# ESP8266-CT-EVB.net
KiCad netlist of a schematic drawn in EAGLE
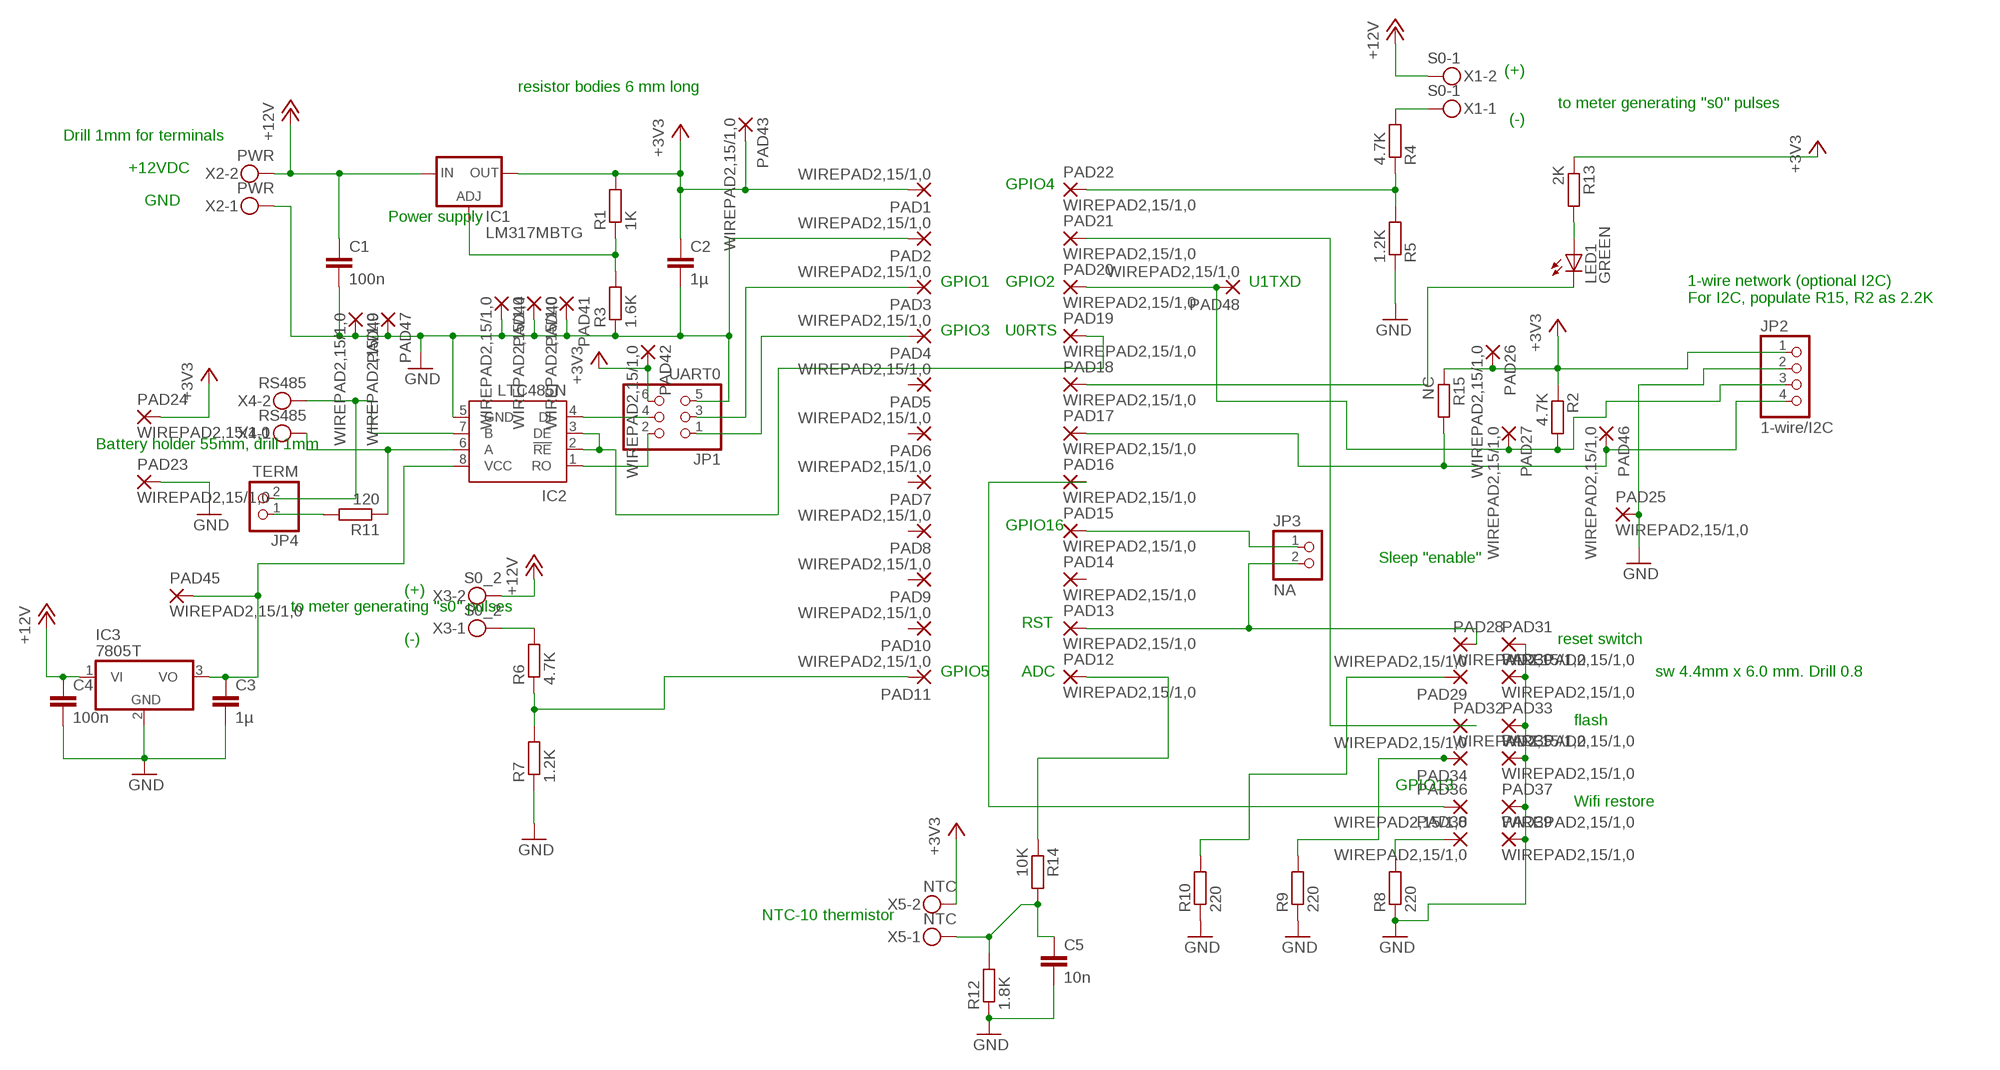
[diagram p0: schematic, sheet 1]

(export (version "E")
  (design (tool "Eeschema 10.0.6"))
  (components
    (comp (ref "C1")
      (value "100n")
      (footprint "eagle-import:C050-024X044")
      (libsource (lib "eagle-import") (part "C-EU050-024X044"))
    )
    (comp (ref "C2")
      (value "1µ")
      (footprint "eagle-import:C050-024X044")
      (libsource (lib "eagle-import") (part "C-EU050-024X044"))
    )
    (comp (ref "C3")
      (value "1µ")
      (footprint "eagle-import:C050-024X044")
      (libsource (lib "eagle-import") (part "C-EU050-024X044"))
    )
    (comp (ref "C4")
      (value "100n")
      (footprint "eagle-import:C050-024X044")
      (libsource (lib "eagle-import") (part "C-EU050-024X044"))
    )
    (comp (ref "C5")
      (value "10n")
      (footprint "eagle-import:C050-024X044")
      (libsource (lib "eagle-import") (part "C-EU050-024X044"))
    )
    (comp (ref "IC1")
      (value "LM317MBTG")
      (footprint "eagle-import:TO220L1")
      (libsource (lib "eagle-import") (part "LM317?MBTG"))
    )
    (comp (ref "IC2")
      (value "LTC485N")
      (footprint "eagle-import:DIL08")
      (libsource (lib "eagle-import") (part "LTC485N"))
    )
    (comp (ref "IC3")
      (value "7805T")
      (footprint "eagle-import:TO220H")
      (libsource (lib "eagle-import") (part "78T05"))
    )
    (comp (ref "JP1")
      (value "UART0")
      (footprint "eagle-import:2X03")
      (libsource (lib "eagle-import") (part "PINHD-2X3"))
    )
    (comp (ref "JP2")
      (value "1-wire/I2C")
      (footprint "eagle-import:1X04")
      (libsource (lib "eagle-import") (part "PINHD-1X4"))
    )
    (comp (ref "JP3")
      (value "NA")
      (footprint "eagle-import:1X02")
      (libsource (lib "eagle-import") (part "PINHD-1X2"))
    )
    (comp (ref "JP4")
      (value "TERM")
      (footprint "eagle-import:1X02")
      (libsource (lib "eagle-import") (part "PINHD-1X2"))
    )
    (comp (ref "LED1")
      (value "GREEN")
      (footprint "eagle-import:LED3MM")
      (libsource (lib "eagle-import") (part "LED3MM"))
    )
    (comp (ref "PAD1")
      (value "WIREPAD2,15/1,0")
      (footprint "eagle-import:2,15_1,0")
      (libsource (lib "eagle-import") (part "WIREPAD2,15/1,0"))
    )
    (comp (ref "PAD2")
      (value "WIREPAD2,15/1,0")
      (footprint "eagle-import:2,15_1,0")
      (libsource (lib "eagle-import") (part "WIREPAD2,15/1,0"))
    )
    (comp (ref "PAD3")
      (value "WIREPAD2,15/1,0")
      (footprint "eagle-import:2,15_1,0")
      (libsource (lib "eagle-import") (part "WIREPAD2,15/1,0"))
    )
    (comp (ref "PAD4")
      (value "WIREPAD2,15/1,0")
      (footprint "eagle-import:2,15_1,0")
      (libsource (lib "eagle-import") (part "WIREPAD2,15/1,0"))
    )
    (comp (ref "PAD5")
      (value "WIREPAD2,15/1,0")
      (footprint "eagle-import:2,15_1,0")
      (libsource (lib "eagle-import") (part "WIREPAD2,15/1,0"))
    )
    (comp (ref "PAD6")
      (value "WIREPAD2,15/1,0")
      (footprint "eagle-import:2,15_1,0")
      (libsource (lib "eagle-import") (part "WIREPAD2,15/1,0"))
    )
    (comp (ref "PAD7")
      (value "WIREPAD2,15/1,0")
      (footprint "eagle-import:2,15_1,0")
      (libsource (lib "eagle-import") (part "WIREPAD2,15/1,0"))
    )
    (comp (ref "PAD8")
      (value "WIREPAD2,15/1,0")
      (footprint "eagle-import:2,15_1,0")
      (libsource (lib "eagle-import") (part "WIREPAD2,15/1,0"))
    )
    (comp (ref "PAD9")
      (value "WIREPAD2,15/1,0")
      (footprint "eagle-import:2,15_1,0")
      (libsource (lib "eagle-import") (part "WIREPAD2,15/1,0"))
    )
    (comp (ref "PAD10")
      (value "WIREPAD2,15/1,0")
      (footprint "eagle-import:2,15_1,0")
      (libsource (lib "eagle-import") (part "WIREPAD2,15/1,0"))
    )
    (comp (ref "PAD11")
      (value "WIREPAD2,15/1,0")
      (footprint "eagle-import:2,15_1,0")
      (libsource (lib "eagle-import") (part "WIREPAD2,15/1,0"))
    )
    (comp (ref "PAD12")
      (value "WIREPAD2,15/1,0")
      (footprint "eagle-import:2,15_1,0")
      (libsource (lib "eagle-import") (part "WIREPAD2,15/1,0"))
    )
    (comp (ref "PAD13")
      (value "WIREPAD2,15/1,0")
      (footprint "eagle-import:2,15_1,0")
      (libsource (lib "eagle-import") (part "WIREPAD2,15/1,0"))
    )
    (comp (ref "PAD14")
      (value "WIREPAD2,15/1,0")
      (footprint "eagle-import:2,15_1,0")
      (libsource (lib "eagle-import") (part "WIREPAD2,15/1,0"))
    )
    (comp (ref "PAD15")
      (value "WIREPAD2,15/1,0")
      (footprint "eagle-import:2,15_1,0")
      (libsource (lib "eagle-import") (part "WIREPAD2,15/1,0"))
    )
    (comp (ref "PAD16")
      (value "WIREPAD2,15/1,0")
      (footprint "eagle-import:2,15_1,0")
      (libsource (lib "eagle-import") (part "WIREPAD2,15/1,0"))
    )
    (comp (ref "PAD17")
      (value "WIREPAD2,15/1,0")
      (footprint "eagle-import:2,15_1,0")
      (libsource (lib "eagle-import") (part "WIREPAD2,15/1,0"))
    )
    (comp (ref "PAD18")
      (value "WIREPAD2,15/1,0")
      (footprint "eagle-import:2,15_1,0")
      (libsource (lib "eagle-import") (part "WIREPAD2,15/1,0"))
    )
    (comp (ref "PAD19")
      (value "WIREPAD2,15/1,0")
      (footprint "eagle-import:2,15_1,0")
      (libsource (lib "eagle-import") (part "WIREPAD2,15/1,0"))
    )
    (comp (ref "PAD20")
      (value "WIREPAD2,15/1,0")
      (footprint "eagle-import:2,15_1,0")
      (libsource (lib "eagle-import") (part "WIREPAD2,15/1,0"))
    )
    (comp (ref "PAD21")
      (value "WIREPAD2,15/1,0")
      (footprint "eagle-import:2,15_1,0")
      (libsource (lib "eagle-import") (part "WIREPAD2,15/1,0"))
    )
    (comp (ref "PAD22")
      (value "WIREPAD2,15/1,0")
      (footprint "eagle-import:2,15_1,0")
      (libsource (lib "eagle-import") (part "WIREPAD2,15/1,0"))
    )
    (comp (ref "PAD23")
      (value "WIREPAD2,15/1,0")
      (footprint "eagle-import:2,15_1,0")
      (libsource (lib "eagle-import") (part "WIREPAD2,15/1,0"))
    )
    (comp (ref "PAD24")
      (value "WIREPAD2,15/1,0")
      (footprint "eagle-import:2,15_1,0")
      (libsource (lib "eagle-import") (part "WIREPAD2,15/1,0"))
    )
    (comp (ref "PAD25")
      (value "WIREPAD2,15/1,0")
      (footprint "eagle-import:2,15_1,0")
      (libsource (lib "eagle-import") (part "WIREPAD2,15/1,0"))
    )
    (comp (ref "PAD26")
      (value "WIREPAD2,15/1,0")
      (footprint "eagle-import:2,15_1,0")
      (libsource (lib "eagle-import") (part "WIREPAD2,15/1,0"))
    )
    (comp (ref "PAD27")
      (value "WIREPAD2,15/1,0")
      (footprint "eagle-import:2,15_1,0")
      (libsource (lib "eagle-import") (part "WIREPAD2,15/1,0"))
    )
    (comp (ref "PAD28")
      (value "WIREPAD2,15/1,0")
      (footprint "eagle-import:2,15_1,0")
      (libsource (lib "eagle-import") (part "WIREPAD2,15/1,0"))
    )
    (comp (ref "PAD29")
      (value "WIREPAD2,15/1,0")
      (footprint "eagle-import:2,15_1,0")
      (libsource (lib "eagle-import") (part "WIREPAD2,15/1,0"))
    )
    (comp (ref "PAD30")
      (value "WIREPAD2,15/1,0")
      (footprint "eagle-import:2,15_1,0")
      (libsource (lib "eagle-import") (part "WIREPAD2,15/1,0"))
    )
    (comp (ref "PAD31")
      (value "WIREPAD2,15/1,0")
      (footprint "eagle-import:2,15_1,0")
      (libsource (lib "eagle-import") (part "WIREPAD2,15/1,0"))
    )
    (comp (ref "PAD32")
      (value "WIREPAD2,15/1,0")
      (footprint "eagle-import:2,15_1,0")
      (libsource (lib "eagle-import") (part "WIREPAD2,15/1,0"))
    )
    (comp (ref "PAD33")
      (value "WIREPAD2,15/1,0")
      (footprint "eagle-import:2,15_1,0")
      (libsource (lib "eagle-import") (part "WIREPAD2,15/1,0"))
    )
    (comp (ref "PAD34")
      (value "WIREPAD2,15/1,0")
      (footprint "eagle-import:2,15_1,0")
      (libsource (lib "eagle-import") (part "WIREPAD2,15/1,0"))
    )
    (comp (ref "PAD35")
      (value "WIREPAD2,15/1,0")
      (footprint "eagle-import:2,15_1,0")
      (libsource (lib "eagle-import") (part "WIREPAD2,15/1,0"))
    )
    (comp (ref "PAD36")
      (value "WIREPAD2,15/1,0")
      (footprint "eagle-import:2,15_1,0")
      (libsource (lib "eagle-import") (part "WIREPAD2,15/1,0"))
    )
    (comp (ref "PAD37")
      (value "WIREPAD2,15/1,0")
      (footprint "eagle-import:2,15_1,0")
      (libsource (lib "eagle-import") (part "WIREPAD2,15/1,0"))
    )
    (comp (ref "PAD38")
      (value "WIREPAD2,15/1,0")
      (footprint "eagle-import:2,15_1,0")
      (libsource (lib "eagle-import") (part "WIREPAD2,15/1,0"))
    )
    (comp (ref "PAD39")
      (value "WIREPAD2,15/1,0")
      (footprint "eagle-import:2,15_1,0")
      (libsource (lib "eagle-import") (part "WIREPAD2,15/1,0"))
    )
    (comp (ref "PAD40")
      (value "WIREPAD2,15/1,0")
      (footprint "eagle-import:2,15_1,0")
      (libsource (lib "eagle-import") (part "WIREPAD2,15/1,0"))
    )
    (comp (ref "PAD41")
      (value "WIREPAD2,15/1,0")
      (footprint "eagle-import:2,15_1,0")
      (libsource (lib "eagle-import") (part "WIREPAD2,15/1,0"))
    )
    (comp (ref "PAD42")
      (value "WIREPAD2,15/1,0")
      (footprint "eagle-import:2,15_1,0")
      (libsource (lib "eagle-import") (part "WIREPAD2,15/1,0"))
    )
    (comp (ref "PAD43")
      (value "WIREPAD2,15/1,0")
      (footprint "eagle-import:2,15_1,0")
      (libsource (lib "eagle-import") (part "WIREPAD2,15/1,0"))
    )
    (comp (ref "PAD44")
      (value "WIREPAD2,15/1,0")
      (footprint "eagle-import:2,15_1,0")
      (libsource (lib "eagle-import") (part "WIREPAD2,15/1,0"))
    )
    (comp (ref "PAD45")
      (value "WIREPAD2,15/1,0")
      (footprint "eagle-import:2,15_1,0")
      (libsource (lib "eagle-import") (part "WIREPAD2,15/1,0"))
    )
    (comp (ref "PAD46")
      (value "WIREPAD2,15/1,0")
      (footprint "eagle-import:2,15_1,0")
      (libsource (lib "eagle-import") (part "WIREPAD2,15/1,0"))
    )
    (comp (ref "PAD47")
      (value "WIREPAD2,15/1,0")
      (footprint "eagle-import:2,15_1,0")
      (libsource (lib "eagle-import") (part "WIREPAD2,15/1,0"))
    )
    (comp (ref "PAD48")
      (value "WIREPAD2,15/1,0")
      (footprint "eagle-import:2,15_1,0")
      (libsource (lib "eagle-import") (part "WIREPAD2,15/1,0"))
    )
    (comp (ref "PAD49")
      (value "WIREPAD2,15/1,0")
      (footprint "eagle-import:2,15_1,0")
      (libsource (lib "eagle-import") (part "WIREPAD2,15/1,0"))
    )
    (comp (ref "R1")
      (value "1K")
      (footprint "eagle-import:0207_10")
      (libsource (lib "eagle-import") (part "resistor_R-EU_0207/10"))
    )
    (comp (ref "R2")
      (value "4.7K")
      (footprint "eagle-import:0207_2V")
      (libsource (lib "eagle-import") (part "R-EU_0207/2V"))
    )
    (comp (ref "R3")
      (value "1.6K")
      (footprint "eagle-import:0207_10")
      (libsource (lib "eagle-import") (part "resistor_R-EU_0207/10"))
    )
    (comp (ref "R4")
      (value "4.7K")
      (footprint "eagle-import:0207_10")
      (libsource (lib "eagle-import") (part "resistor_R-EU_0207/10"))
    )
    (comp (ref "R5")
      (value "1.2K")
      (footprint "eagle-import:0207_10")
      (libsource (lib "eagle-import") (part "resistor_R-EU_0207/10"))
    )
    (comp (ref "R6")
      (value "4.7K")
      (footprint "eagle-import:0207_10")
      (libsource (lib "eagle-import") (part "resistor_R-EU_0207/10"))
    )
    (comp (ref "R7")
      (value "1.2K")
      (footprint "eagle-import:0207_10")
      (libsource (lib "eagle-import") (part "resistor_R-EU_0207/10"))
    )
    (comp (ref "R8")
      (value "220")
      (footprint "eagle-import:0207_2V")
      (libsource (lib "eagle-import") (part "R-EU_0207/2V"))
    )
    (comp (ref "R9")
      (value "220")
      (footprint "eagle-import:0207_2V")
      (libsource (lib "eagle-import") (part "R-EU_0207/2V"))
    )
    (comp (ref "R10")
      (value "220")
      (footprint "eagle-import:0207_2V")
      (libsource (lib "eagle-import") (part "R-EU_0207/2V"))
    )
    (comp (ref "R11")
      (value "120")
      (footprint "eagle-import:0207_2V")
      (libsource (lib "eagle-import") (part "R-EU_0207/2V"))
    )
    (comp (ref "R12")
      (value "1.8K")
      (footprint "eagle-import:0207_10")
      (libsource (lib "eagle-import") (part "resistor_R-EU_0207/10"))
    )
    (comp (ref "R13")
      (value "2K")
      (footprint "eagle-import:0207_7")
      (libsource (lib "eagle-import") (part "R-EU_0207/7"))
    )
    (comp (ref "R14")
      (value "10K")
      (footprint "eagle-import:0207_2V")
      (libsource (lib "eagle-import") (part "R-EU_0207/2V"))
    )
    (comp (ref "R15")
      (value "NC")
      (footprint "eagle-import:0207_2V")
      (libsource (lib "eagle-import") (part "R-EU_0207/2V"))
    )
    (comp (ref "X1")
      (value "S0-1")
      (footprint "eagle-import:MKDSN1,5_2-5,08")
      (libsource (lib "eagle-import") (part "MKDSN1,5/2-5,08"))
    )
    (comp (ref "X2")
      (value "PWR")
      (footprint "eagle-import:MKDSN1,5_2-5,08")
      (libsource (lib "eagle-import") (part "MKDSN1,5/2-5,08"))
    )
    (comp (ref "X3")
      (value "S0_2")
      (footprint "eagle-import:MKDSN1,5_2-5,08")
      (libsource (lib "eagle-import") (part "MKDSN1,5/2-5,08"))
    )
    (comp (ref "X4")
      (value "RS485")
      (footprint "eagle-import:MKDSN1,5_2-5,08")
      (libsource (lib "eagle-import") (part "MKDSN1,5/2-5,08"))
    )
    (comp (ref "X5")
      (value "NTC")
      (footprint "eagle-import:MKDSN1,5_2-5,08")
      (libsource (lib "eagle-import") (part "MKDSN1,5/2-5,08"))
    )
  )
  (nets
    (net (code "1") (name "+3V3") (class "Default")
      (node (ref "C2") (pin "1") (pinfunction "1_1") (pintype "passive"))
      (node (ref "IC1") (pin "2") (pinfunction "OUT_2") (pintype "passive"))
      (node (ref "JP1") (pin "6") (pinfunction "6_6") (pintype "passive"))
      (node (ref "JP2") (pin "1") (pinfunction "1_1") (pintype "passive"))
      (node (ref "PAD1") (pin "1") (pinfunction "P_1") (pintype "passive"))
      (node (ref "PAD24") (pin "1") (pinfunction "P_1") (pintype "passive"))
      (node (ref "PAD26") (pin "1") (pinfunction "P_1") (pintype "passive"))
      (node (ref "PAD42") (pin "1") (pinfunction "P_1") (pintype "passive"))
      (node (ref "PAD43") (pin "1") (pinfunction "P_1") (pintype "passive"))
      (node (ref "R1") (pin "2") (pinfunction "2_2") (pintype "passive"))
      (node (ref "R13") (pin "1") (pinfunction "1_1") (pintype "passive"))
      (node (ref "R15") (pin "1") (pinfunction "1_1") (pintype "passive"))
      (node (ref "R2") (pin "1") (pinfunction "1_1") (pintype "passive"))
      (node (ref "X5") (pin "2") (pinfunction "KL_2") (pintype "passive"))
    )
    (net (code "2") (name "+12V") (class "Default")
      (node (ref "C1") (pin "1") (pinfunction "1_1") (pintype "passive"))
      (node (ref "C4") (pin "1") (pinfunction "1_1") (pintype "passive"))
      (node (ref "IC1") (pin "3") (pinfunction "IN_3") (pintype "input"))
      (node (ref "IC3") (pin "1") (pinfunction "VI_1") (pintype "input"))
      (node (ref "X1") (pin "2") (pinfunction "KL_2") (pintype "passive"))
      (node (ref "X2") (pin "2") (pinfunction "KL_2") (pintype "passive"))
      (node (ref "X3") (pin "2") (pinfunction "KL_2") (pintype "passive"))
    )
    (net (code "3") (name "GND") (class "Default")
      (node (ref "C1") (pin "2") (pinfunction "2_2") (pintype "passive"))
      (node (ref "C2") (pin "2") (pinfunction "2_2") (pintype "passive"))
      (node (ref "C3") (pin "2") (pinfunction "2_2") (pintype "passive"))
      (node (ref "C4") (pin "2") (pinfunction "2_2") (pintype "passive"))
      (node (ref "C5") (pin "2") (pinfunction "2_2") (pintype "passive"))
      (node (ref "IC2") (pin "5") (pinfunction "GND_5") (pintype "input"))
      (node (ref "IC3") (pin "2") (pinfunction "GND_2") (pintype "passive"))
      (node (ref "JP1") (pin "5") (pinfunction "5_5") (pintype "passive"))
      (node (ref "JP2") (pin "2") (pinfunction "2_2") (pintype "passive"))
      (node (ref "PAD2") (pin "1") (pinfunction "P_1") (pintype "passive"))
      (node (ref "PAD23") (pin "1") (pinfunction "P_1") (pintype "passive"))
      (node (ref "PAD25") (pin "1") (pinfunction "P_1") (pintype "passive"))
      (node (ref "PAD30") (pin "1") (pinfunction "P_1") (pintype "passive"))
      (node (ref "PAD31") (pin "1") (pinfunction "P_1") (pintype "passive"))
      (node (ref "PAD33") (pin "1") (pinfunction "P_1") (pintype "passive"))
      (node (ref "PAD35") (pin "1") (pinfunction "P_1") (pintype "passive"))
      (node (ref "PAD37") (pin "1") (pinfunction "P_1") (pintype "passive"))
      (node (ref "PAD39") (pin "1") (pinfunction "P_1") (pintype "passive"))
      (node (ref "PAD40") (pin "1") (pinfunction "P_1") (pintype "passive"))
      (node (ref "PAD41") (pin "1") (pinfunction "P_1") (pintype "passive"))
      (node (ref "PAD44") (pin "1") (pinfunction "P_1") (pintype "passive"))
      (node (ref "PAD47") (pin "1") (pinfunction "P_1") (pintype "passive"))
      (node (ref "PAD49") (pin "1") (pinfunction "P_1") (pintype "passive"))
      (node (ref "R10") (pin "1") (pinfunction "1_1") (pintype "passive"))
      (node (ref "R12") (pin "1") (pinfunction "1_1") (pintype "passive"))
      (node (ref "R3") (pin "1") (pinfunction "1_1") (pintype "passive"))
      (node (ref "R5") (pin "1") (pinfunction "1_1") (pintype "passive"))
      (node (ref "R7") (pin "1") (pinfunction "1_1") (pintype "passive"))
      (node (ref "R8") (pin "1") (pinfunction "1_1") (pintype "passive"))
      (node (ref "R9") (pin "1") (pinfunction "1_1") (pintype "passive"))
      (node (ref "X2") (pin "1") (pinfunction "KL_1") (pintype "passive"))
    )
    (net (code "4") (name "Net-(IC1-ADJ)") (class "Default")
      (node (ref "IC1") (pin "1") (pinfunction "ADJ_1") (pintype "input"))
      (node (ref "R1") (pin "1") (pinfunction "1_1") (pintype "passive"))
      (node (ref "R3") (pin "2") (pinfunction "2_2") (pintype "passive"))
    )
    (net (code "5") (name "Net-(IC2-A)") (class "Default")
      (node (ref "IC2") (pin "6") (pinfunction "A_6") (pintype "bidirectional"))
      (node (ref "R11") (pin "1") (pinfunction "1_1") (pintype "passive"))
      (node (ref "X4") (pin "1") (pinfunction "KL_1") (pintype "passive"))
    )
    (net (code "6") (name "Net-(IC2-B)") (class "Default")
      (node (ref "IC2") (pin "7") (pinfunction "B_7") (pintype "bidirectional"))
      (node (ref "JP4") (pin "2") (pinfunction "2_2") (pintype "passive"))
      (node (ref "X4") (pin "2") (pinfunction "KL_2") (pintype "passive"))
    )
    (net (code "7") (name "Net-(IC2-DE)") (class "Default")
      (node (ref "IC2") (pin "2") (pinfunction "~{RE}_2") (pintype "input"))
      (node (ref "IC2") (pin "3") (pinfunction "DE_3") (pintype "input"))
      (node (ref "PAD19") (pin "1") (pinfunction "P_1") (pintype "passive"))
    )
    (net (code "8") (name "Net-(IC2-DI)") (class "Default")
      (node (ref "IC2") (pin "4") (pinfunction "DI_4") (pintype "input"))
      (node (ref "JP1") (pin "4") (pinfunction "4_4") (pintype "passive"))
    )
    (net (code "9") (name "Net-(IC2-RO)") (class "Default")
      (node (ref "IC2") (pin "1") (pinfunction "RO_1") (pintype "output"))
      (node (ref "JP1") (pin "2") (pinfunction "2_2") (pintype "passive"))
    )
    (net (code "10") (name "Net-(IC2-VCC)") (class "Default")
      (node (ref "C3") (pin "1") (pinfunction "1_1") (pintype "passive"))
      (node (ref "IC2") (pin "8") (pinfunction "VCC_8") (pintype "input"))
      (node (ref "IC3") (pin "3") (pinfunction "VO_3") (pintype "passive"))
      (node (ref "PAD45") (pin "1") (pinfunction "P_1") (pintype "passive"))
    )
    (net (code "11") (name "Net-(JP4-Pad1)") (class "Default")
      (node (ref "JP4") (pin "1") (pinfunction "1_1") (pintype "passive"))
      (node (ref "R11") (pin "2") (pinfunction "2_2") (pintype "passive"))
    )
    (net (code "12") (name "Net-(LED1-C)") (class "Default")
      (node (ref "LED1") (pin "K") (pinfunction "C_K") (pintype "passive"))
      (node (ref "PAD18") (pin "1") (pinfunction "P_1") (pintype "passive"))
    )
    (net (code "13") (name "Net-(LED1-PadA)") (class "Default")
      (node (ref "LED1") (pin "A") (pinfunction "A_A") (pintype "passive"))
      (node (ref "R13") (pin "2") (pinfunction "2_2") (pintype "passive"))
    )
    (net (code "14") (name "Net-(PAD3-P)") (class "Default")
      (node (ref "JP1") (pin "3") (pinfunction "3_3") (pintype "passive"))
      (node (ref "PAD3") (pin "1") (pinfunction "P_1") (pintype "passive"))
    )
    (net (code "15") (name "Net-(PAD4-P)") (class "Default")
      (node (ref "JP1") (pin "1") (pinfunction "1_1") (pintype "passive"))
      (node (ref "PAD4") (pin "1") (pinfunction "P_1") (pintype "passive"))
    )
    (net (code "16") (name "Net-(PAD11-P)") (class "Default")
      (node (ref "PAD11") (pin "1") (pinfunction "P_1") (pintype "passive"))
      (node (ref "R6") (pin "1") (pinfunction "1_1") (pintype "passive"))
      (node (ref "R7") (pin "2") (pinfunction "2_2") (pintype "passive"))
    )
    (net (code "17") (name "Net-(PAD12-P)") (class "Default")
      (node (ref "PAD12") (pin "1") (pinfunction "P_1") (pintype "passive"))
      (node (ref "R14") (pin "1") (pinfunction "1_1") (pintype "passive"))
    )
    (net (code "18") (name "Net-(PAD13-P)") (class "Default")
      (node (ref "JP3") (pin "2") (pinfunction "2_2") (pintype "passive"))
      (node (ref "PAD13") (pin "1") (pinfunction "P_1") (pintype "passive"))
      (node (ref "PAD28") (pin "1") (pinfunction "P_1") (pintype "passive"))
    )
    (net (code "19") (name "Net-(PAD15-P)") (class "Default")
      (node (ref "JP3") (pin "1") (pinfunction "1_1") (pintype "passive"))
      (node (ref "PAD15") (pin "1") (pinfunction "P_1") (pintype "passive"))
    )
    (net (code "20") (name "Net-(PAD16-P)") (class "Default")
      (node (ref "PAD16") (pin "1") (pinfunction "P_1") (pintype "passive"))
      (node (ref "PAD36") (pin "1") (pinfunction "P_1") (pintype "passive"))
    )
    (net (code "21") (name "Net-(PAD17-P)") (class "Default")
      (node (ref "JP2") (pin "4") (pinfunction "4_4") (pintype "passive"))
      (node (ref "PAD17") (pin "1") (pinfunction "P_1") (pintype "passive"))
      (node (ref "PAD46") (pin "1") (pinfunction "P_1") (pintype "passive"))
      (node (ref "R15") (pin "2") (pinfunction "2_2") (pintype "passive"))
    )
    (net (code "22") (name "Net-(PAD20-P)") (class "Default")
      (node (ref "JP2") (pin "3") (pinfunction "3_3") (pintype "passive"))
      (node (ref "PAD20") (pin "1") (pinfunction "P_1") (pintype "passive"))
      (node (ref "PAD27") (pin "1") (pinfunction "P_1") (pintype "passive"))
      (node (ref "PAD48") (pin "1") (pinfunction "P_1") (pintype "passive"))
      (node (ref "R2") (pin "2") (pinfunction "2_2") (pintype "passive"))
    )
    (net (code "23") (name "Net-(PAD21-P)") (class "Default")
      (node (ref "PAD21") (pin "1") (pinfunction "P_1") (pintype "passive"))
      (node (ref "PAD32") (pin "1") (pinfunction "P_1") (pintype "passive"))
    )
    (net (code "24") (name "Net-(PAD22-P)") (class "Default")
      (node (ref "PAD22") (pin "1") (pinfunction "P_1") (pintype "passive"))
      (node (ref "R4") (pin "1") (pinfunction "1_1") (pintype "passive"))
      (node (ref "R5") (pin "2") (pinfunction "2_2") (pintype "passive"))
    )
    (net (code "25") (name "Net-(PAD29-P)") (class "Default")
      (node (ref "PAD29") (pin "1") (pinfunction "P_1") (pintype "passive"))
      (node (ref "R10") (pin "2") (pinfunction "2_2") (pintype "passive"))
    )
    (net (code "26") (name "Net-(PAD34-P)") (class "Default")
      (node (ref "PAD34") (pin "1") (pinfunction "P_1") (pintype "passive"))
      (node (ref "R9") (pin "2") (pinfunction "2_2") (pintype "passive"))
    )
    (net (code "27") (name "Net-(PAD38-P)") (class "Default")
      (node (ref "PAD38") (pin "1") (pinfunction "P_1") (pintype "passive"))
      (node (ref "R8") (pin "2") (pinfunction "2_2") (pintype "passive"))
    )
    (net (code "28") (name "Net-(X1A-KL)") (class "Default")
      (node (ref "R4") (pin "2") (pinfunction "2_2") (pintype "passive"))
      (node (ref "X1") (pin "1") (pinfunction "KL_1") (pintype "passive"))
    )
    (net (code "29") (name "Net-(X3A-KL)") (class "Default")
      (node (ref "R6") (pin "2") (pinfunction "2_2") (pintype "passive"))
      (node (ref "X3") (pin "1") (pinfunction "KL_1") (pintype "passive"))
    )
    (net (code "30") (name "Net-(X5A-KL)") (class "Default")
      (node (ref "C5") (pin "1") (pinfunction "1_1") (pintype "passive"))
      (node (ref "R12") (pin "2") (pinfunction "2_2") (pintype "passive"))
      (node (ref "R14") (pin "2") (pinfunction "2_2") (pintype "passive"))
      (node (ref "X5") (pin "1") (pinfunction "KL_1") (pintype "passive"))
    )
    (net (code "31") (name "unconnected-(PAD5-P-Pad1)") (class "Default")
      (node (ref "PAD5") (pin "1") (pinfunction "P_1") (pintype "passive"))
    )
    (net (code "32") (name "unconnected-(PAD6-P-Pad1)") (class "Default")
      (node (ref "PAD6") (pin "1") (pinfunction "P_1") (pintype "passive"))
    )
    (net (code "33") (name "unconnected-(PAD7-P-Pad1)") (class "Default")
      (node (ref "PAD7") (pin "1") (pinfunction "P_1") (pintype "passive"))
    )
    (net (code "34") (name "unconnected-(PAD8-P-Pad1)") (class "Default")
      (node (ref "PAD8") (pin "1") (pinfunction "P_1") (pintype "passive"))
    )
    (net (code "35") (name "unconnected-(PAD9-P-Pad1)") (class "Default")
      (node (ref "PAD9") (pin "1") (pinfunction "P_1") (pintype "passive"))
    )
    (net (code "36") (name "unconnected-(PAD10-P-Pad1)") (class "Default")
      (node (ref "PAD10") (pin "1") (pinfunction "P_1") (pintype "passive"))
    )
    (net (code "37") (name "unconnected-(PAD14-P-Pad1)") (class "Default")
      (node (ref "PAD14") (pin "1") (pinfunction "P_1") (pintype "passive"))
    )
  )
)
